# Sheet3.net
KiCad netlist of a schematic drawn in Altium Designer
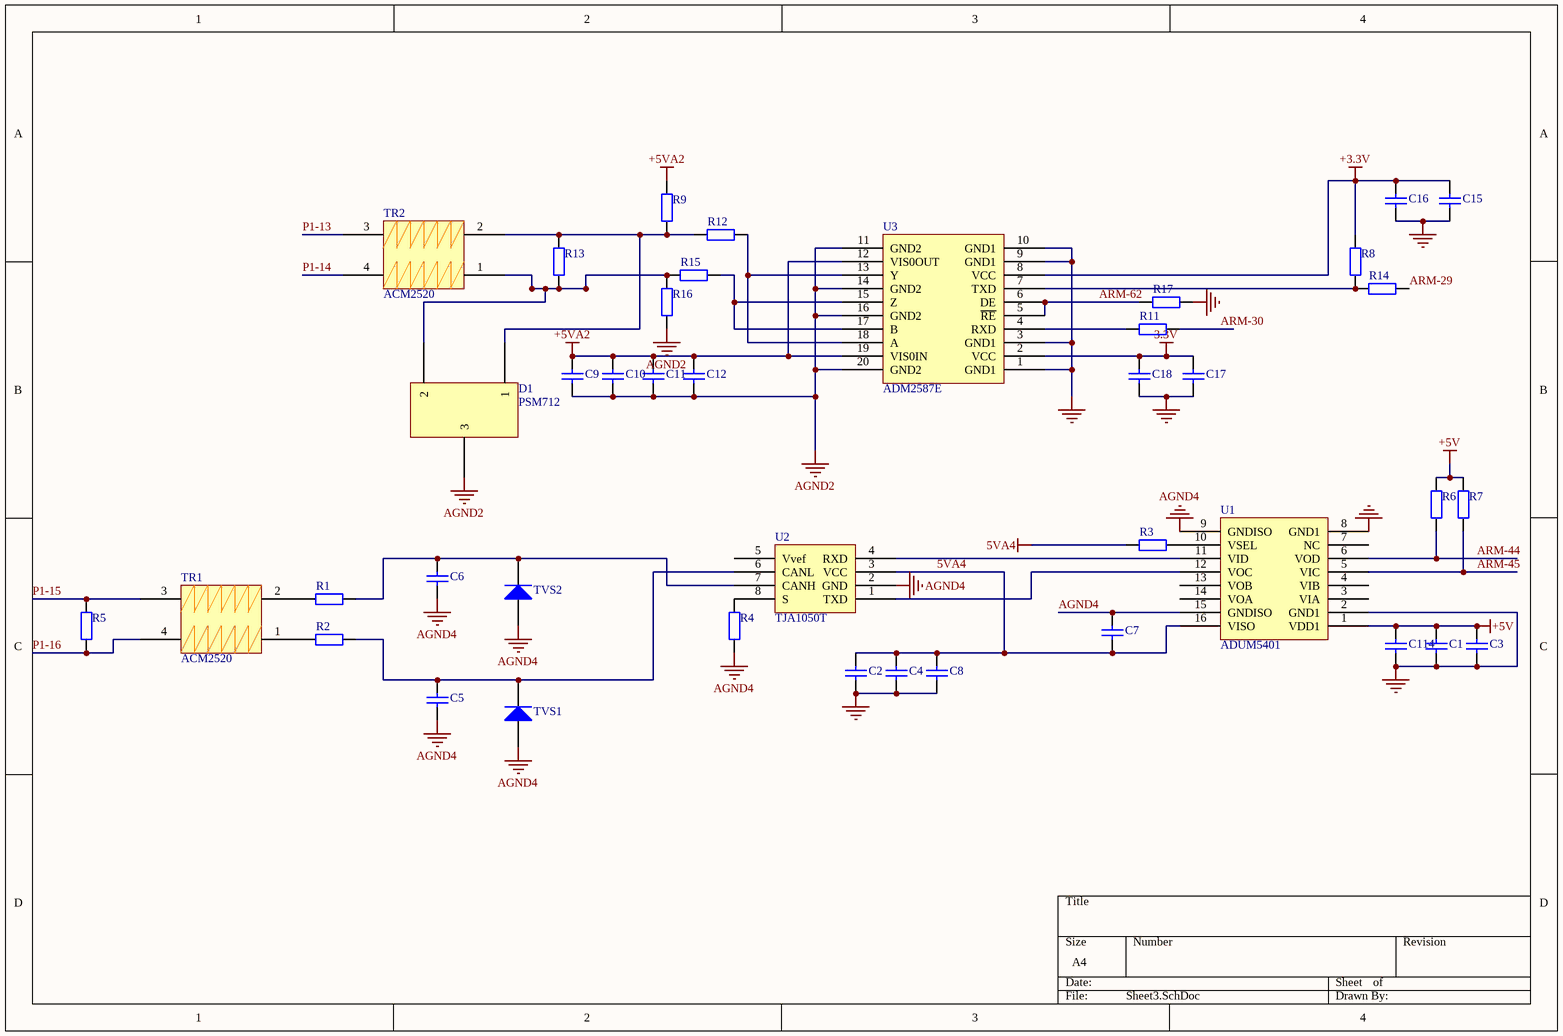
[diagram p0: Sheet3.SchDoc]

(export (version "E")
  (design (tool "Eeschema 10.0.6"))
  (components
    (comp (ref "C1")
      (value "Cap")
      (footprint "RAD-0.3")
      (description "Capacitor")
      (fields (field (name "PUBLISHER") "Altium Limited"))
      (libsource (lib "Miscellaneous Devices") (part "Cap"))
    )
    (comp (ref "C2")
      (value "Cap")
      (footprint "RAD-0.3")
      (description "Capacitor")
      (fields (field (name "PUBLISHER") "Altium Limited"))
      (libsource (lib "Miscellaneous Devices") (part "Cap"))
    )
    (comp (ref "C3")
      (value "Cap")
      (footprint "RAD-0.3")
      (description "Capacitor")
      (fields (field (name "PUBLISHER") "Altium Limited"))
      (libsource (lib "Miscellaneous Devices") (part "Cap"))
    )
    (comp (ref "C4")
      (value "Cap")
      (footprint "RAD-0.3")
      (description "Capacitor")
      (fields (field (name "PUBLISHER") "Altium Limited"))
      (libsource (lib "Miscellaneous Devices") (part "Cap"))
    )
    (comp (ref "C5")
      (value "Cap")
      (footprint "RAD-0.3")
      (description "Capacitor")
      (fields (field (name "PUBLISHER") "Altium Limited"))
      (libsource (lib "Miscellaneous Devices") (part "Cap"))
    )
    (comp (ref "C6")
      (value "Cap")
      (footprint "RAD-0.3")
      (description "Capacitor")
      (fields (field (name "PUBLISHER") "Altium Limited"))
      (libsource (lib "Miscellaneous Devices") (part "Cap"))
    )
    (comp (ref "C7")
      (value "Cap")
      (footprint "RAD-0.3")
      (description "Capacitor")
      (fields (field (name "PUBLISHER") "Altium Limited"))
      (libsource (lib "Miscellaneous Devices") (part "Cap"))
    )
    (comp (ref "C8")
      (value "Cap")
      (footprint "RAD-0.3")
      (description "Capacitor")
      (fields (field (name "PUBLISHER") "Altium Limited"))
      (libsource (lib "Miscellaneous Devices") (part "Cap"))
    )
    (comp (ref "C9")
      (value "Cap")
      (footprint "RAD-0.3")
      (description "Capacitor")
      (fields (field (name "PUBLISHER") "Altium Limited"))
      (libsource (lib "Miscellaneous Devices") (part "Cap"))
    )
    (comp (ref "C10")
      (value "Cap")
      (footprint "RAD-0.3")
      (description "Capacitor")
      (fields (field (name "PUBLISHER") "Altium Limited"))
      (libsource (lib "Miscellaneous Devices") (part "Cap"))
    )
    (comp (ref "C11")
      (value "Cap")
      (footprint "RAD-0.3")
      (description "Capacitor")
      (fields (field (name "PUBLISHER") "Altium Limited"))
      (libsource (lib "Miscellaneous Devices") (part "Cap"))
    )
    (comp (ref "C12")
      (value "Cap")
      (footprint "RAD-0.3")
      (description "Capacitor")
      (fields (field (name "PUBLISHER") "Altium Limited"))
      (libsource (lib "Miscellaneous Devices") (part "Cap"))
    )
    (comp (ref "C15")
      (value "Cap")
      (footprint "RAD-0.3")
      (description "Capacitor")
      (fields (field (name "PUBLISHER") "Altium Limited"))
      (libsource (lib "Miscellaneous Devices") (part "Cap"))
    )
    (comp (ref "C16")
      (value "Cap")
      (footprint "RAD-0.3")
      (description "Capacitor")
      (fields (field (name "PUBLISHER") "Altium Limited"))
      (libsource (lib "Miscellaneous Devices") (part "Cap"))
    )
    (comp (ref "C17")
      (value "Cap")
      (footprint "RAD-0.3")
      (description "Capacitor")
      (fields (field (name "PUBLISHER") "Altium Limited"))
      (libsource (lib "Miscellaneous Devices") (part "Cap"))
    )
    (comp (ref "C18")
      (value "Cap")
      (footprint "RAD-0.3")
      (description "Capacitor")
      (fields (field (name "PUBLISHER") "Altium Limited"))
      (libsource (lib "Miscellaneous Devices") (part "Cap"))
    )
    (comp (ref "C114")
      (value "Cap")
      (footprint "RAD-0.3")
      (description "Capacitor")
      (fields (field (name "PUBLISHER") "Altium Limited"))
      (libsource (lib "Miscellaneous Devices") (part "Cap"))
    )
    (comp (ref "D1") (value "PSM712") (libsource (lib "标准电容阵列") (part "Component_1")))
    (comp (ref "R1")
      (value "Res2")
      (footprint "AXIAL-0.4")
      (description "Resistor")
      (fields (field (name "PUBLISHER") "Altium Limited"))
      (libsource (lib "") (part "Res2_2"))
    )
    (comp (ref "R2")
      (value "Res2")
      (footprint "AXIAL-0.4")
      (description "Resistor")
      (fields (field (name "PUBLISHER") "Altium Limited"))
      (libsource (lib "") (part "Res2_2"))
    )
    (comp (ref "R3")
      (value "Res2")
      (footprint "AXIAL-0.4")
      (description "Resistor")
      (fields (field (name "PUBLISHER") "Altium Limited"))
      (libsource (lib "") (part "Res2_3"))
    )
    (comp (ref "R4")
      (value "Res2")
      (footprint "AXIAL-0.4")
      (description "Resistor")
      (fields (field (name "PUBLISHER") "Altium Limited"))
      (libsource (lib "") (part "Res2_1"))
    )
    (comp (ref "R5")
      (value "Res2")
      (footprint "AXIAL-0.4")
      (description "Resistor")
      (fields (field (name "PUBLISHER") "Altium Limited"))
      (libsource (lib "Miscellaneous Devices") (part "Res2"))
    )
    (comp (ref "R6")
      (value "Res2")
      (footprint "AXIAL-0.4")
      (description "Resistor")
      (fields (field (name "PUBLISHER") "Altium Limited"))
      (libsource (lib "Miscellaneous Devices") (part "Res2"))
    )
    (comp (ref "R7")
      (value "Res2")
      (footprint "AXIAL-0.4")
      (description "Resistor")
      (fields (field (name "PUBLISHER") "Altium Limited"))
      (libsource (lib "Miscellaneous Devices") (part "Res2"))
    )
    (comp (ref "R8")
      (value "Res2")
      (footprint "AXIAL-0.4")
      (description "Resistor")
      (fields (field (name "PUBLISHER") "Altium Limited"))
      (libsource (lib "") (part "Res2_1"))
    )
    (comp (ref "R9")
      (value "Res2")
      (footprint "AXIAL-0.4")
      (description "Resistor")
      (fields (field (name "PUBLISHER") "Altium Limited"))
      (libsource (lib "Miscellaneous Devices") (part "Res2"))
    )
    (comp (ref "R11")
      (value "Res2")
      (footprint "AXIAL-0.4")
      (description "Resistor")
      (fields (field (name "PUBLISHER") "Altium Limited"))
      (libsource (lib "") (part "Res2_2"))
    )
    (comp (ref "R12")
      (value "Res2")
      (footprint "AXIAL-0.4")
      (description "Resistor")
      (fields (field (name "PUBLISHER") "Altium Limited"))
      (libsource (lib "") (part "Res2_2"))
    )
    (comp (ref "R13")
      (value "Res2")
      (footprint "AXIAL-0.4")
      (description "Resistor")
      (fields (field (name "PUBLISHER") "Altium Limited"))
      (libsource (lib "Miscellaneous Devices") (part "Res2"))
    )
    (comp (ref "R14")
      (value "Res2")
      (footprint "AXIAL-0.4")
      (description "Resistor")
      (fields (field (name "PUBLISHER") "Altium Limited"))
      (libsource (lib "") (part "Res2_3"))
    )
    (comp (ref "R15")
      (value "Res2")
      (footprint "AXIAL-0.4")
      (description "Resistor")
      (fields (field (name "PUBLISHER") "Altium Limited"))
      (libsource (lib "") (part "Res2_2"))
    )
    (comp (ref "R16")
      (value "Res2")
      (footprint "AXIAL-0.4")
      (description "Resistor")
      (fields (field (name "PUBLISHER") "Altium Limited"))
      (libsource (lib "Miscellaneous Devices") (part "Res2"))
    )
    (comp (ref "R17")
      (value "Res2")
      (footprint "AXIAL-0.4")
      (description "Resistor")
      (fields (field (name "PUBLISHER") "Altium Limited"))
      (libsource (lib "") (part "Res2_2"))
    )
    (comp (ref "TR1") (value "ACM2520") (libsource (lib "ACM共模电感") (part "Component_1")))
    (comp (ref "TR2") (value "ACM2520") (libsource (lib "ACM共模电感") (part "Component_1")))
    (comp (ref "TVS1")
      (value "Diode 1N4007")
      (footprint "DO-41")
      (description "1 Amp General Purpose Rectifier")
      (fields (field (name "PUBLISHER") "Altium Limited"))
      (libsource (lib "Miscellaneous Devices") (part "Diode 1N4007"))
    )
    (comp (ref "TVS2")
      (value "Diode 1N4007")
      (footprint "DO-41")
      (description "1 Amp General Purpose Rectifier")
      (fields (field (name "PUBLISHER") "Altium Limited"))
      (libsource (lib "Miscellaneous Devices") (part "Diode 1N4007"))
    )
    (comp (ref "U1") (value "ADUM5401") (libsource (lib "ADUM5401") (part "Component_1")))
    (comp (ref "U2") (value "TJA1050T") (libsource (lib "TJA1050T") (part "Component_1")))
    (comp (ref "U3") (value "ADM2587E") (libsource (lib "ADM2587E") (part "Component_1")))
  )
  (nets
    (net (code "1") (name "+3.3V") (class "Default")
      (node (ref "C15") (pin "2") (pinfunction "2_2") (pintype "passive"))
      (node (ref "C16") (pin "2") (pinfunction "2_2") (pintype "passive"))
      (node (ref "R8") (pin "1") (pinfunction "1_1") (pintype "passive"))
      (node (ref "U3") (pin "8") (pinfunction "VCC_8") (pintype "passive"))
    )
    (net (code "2") (name "+5V") (class "Default")
      (node (ref "C1") (pin "2") (pinfunction "2_2") (pintype "passive"))
      (node (ref "C114") (pin "2") (pinfunction "2_2") (pintype "passive"))
      (node (ref "C3") (pin "2") (pinfunction "2_2") (pintype "passive"))
      (node (ref "R6") (pin "2") (pinfunction "2_2") (pintype "passive"))
      (node (ref "R7") (pin "2") (pinfunction "2_2") (pintype "passive"))
      (node (ref "U1") (pin "1") (pinfunction "VDD1_1") (pintype "passive"))
    )
    (net (code "3") (name "+5VA2") (class "Default")
      (node (ref "C10") (pin "2") (pinfunction "2_2") (pintype "passive"))
      (node (ref "C11") (pin "2") (pinfunction "2_2") (pintype "passive"))
      (node (ref "C12") (pin "2") (pinfunction "2_2") (pintype "passive"))
      (node (ref "C9") (pin "2") (pinfunction "2_2") (pintype "passive"))
      (node (ref "R9") (pin "2") (pinfunction "2_2") (pintype "passive"))
      (node (ref "U3") (pin "12") (pinfunction "VIS0OUT_12") (pintype "passive"))
      (node (ref "U3") (pin "19") (pinfunction "VIS0IN_19") (pintype "passive"))
    )
    (net (code "4") (name "/ARM-29") (class "Default")
      (node (ref "R14") (pin "2") (pinfunction "2_2") (pintype "passive"))
    )
    (net (code "5") (name "/ARM-30") (class "Default")
      (node (ref "R11") (pin "1") (pinfunction "1_1") (pintype "passive"))
    )
    (net (code "6") (name "/ARM-44") (class "Default")
      (node (ref "R6") (pin "1") (pinfunction "1_1") (pintype "passive"))
      (node (ref "U1") (pin "6") (pinfunction "VOD_6") (pintype "passive"))
    )
    (net (code "7") (name "/ARM-45") (class "Default")
      (node (ref "R7") (pin "1") (pinfunction "1_1") (pintype "passive"))
      (node (ref "U1") (pin "5") (pinfunction "VIC_5") (pintype "passive"))
    )
    (net (code "8") (name "/ARM-62") (class "Default")
      (node (ref "R17") (pin "2") (pinfunction "2_2") (pintype "passive"))
      (node (ref "U3") (pin "5") (pinfunction "~{RE}_5") (pintype "passive"))
      (node (ref "U3") (pin "6") (pinfunction "DE_6") (pintype "passive"))
    )
    (net (code "9") (name "/P1-13") (class "Default")
      (node (ref "TR2") (pin "3") (pinfunction "0_3") (pintype "passive"))
    )
    (net (code "10") (name "/P1-14") (class "Default")
      (node (ref "TR2") (pin "4") (pinfunction "4_4") (pintype "passive"))
    )
    (net (code "11") (name "/P1-15") (class "Default")
      (node (ref "R5") (pin "2") (pinfunction "2_2") (pintype "passive"))
      (node (ref "TR1") (pin "3") (pinfunction "0_3") (pintype "passive"))
    )
    (net (code "12") (name "/P1-16") (class "Default")
      (node (ref "R5") (pin "1") (pinfunction "1_1") (pintype "passive"))
      (node (ref "TR1") (pin "4") (pinfunction "4_4") (pintype "passive"))
    )
    (net (code "13") (name "3.3V") (class "Default")
      (node (ref "C17") (pin "2") (pinfunction "2_2") (pintype "passive"))
      (node (ref "C18") (pin "2") (pinfunction "2_2") (pintype "passive"))
      (node (ref "U3") (pin "2") (pinfunction "VCC_2") (pintype "passive"))
    )
    (net (code "14") (name "5VA4") (class "Default")
      (node (ref "C2") (pin "2") (pinfunction "2_2") (pintype "passive"))
      (node (ref "C4") (pin "2") (pinfunction "2_2") (pintype "passive"))
      (node (ref "C7") (pin "1") (pinfunction "1_1") (pintype "passive"))
      (node (ref "C8") (pin "2") (pinfunction "2_2") (pintype "passive"))
      (node (ref "R3") (pin "1") (pinfunction "1_1") (pintype "passive"))
      (node (ref "U1") (pin "16") (pinfunction "VISO_16") (pintype "passive"))
      (node (ref "U2") (pin "3") (pinfunction "VCC_3") (pintype "passive"))
    )
    (net (code "15") (name "AGND2") (class "Default")
      (node (ref "C10") (pin "1") (pinfunction "1_1") (pintype "passive"))
      (node (ref "C11") (pin "1") (pinfunction "1_1") (pintype "passive"))
      (node (ref "C12") (pin "1") (pinfunction "1_1") (pintype "passive"))
      (node (ref "C9") (pin "1") (pinfunction "1_1") (pintype "passive"))
      (node (ref "D1") (pin "3") (pinfunction "3_3") (pintype "passive"))
      (node (ref "R16") (pin "1") (pinfunction "1_1") (pintype "passive"))
      (node (ref "U3") (pin "11") (pinfunction "GND2_11") (pintype "passive"))
      (node (ref "U3") (pin "14") (pinfunction "GND2_14") (pintype "passive"))
      (node (ref "U3") (pin "16") (pinfunction "GND2_16") (pintype "passive"))
      (node (ref "U3") (pin "20") (pinfunction "GND2_20") (pintype "passive"))
    )
    (net (code "16") (name "AGND4") (class "Default")
      (node (ref "C5") (pin "1") (pinfunction "1_1") (pintype "passive"))
      (node (ref "C6") (pin "1") (pinfunction "1_1") (pintype "passive"))
      (node (ref "C7") (pin "2") (pinfunction "2_2") (pintype "passive"))
      (node (ref "R4") (pin "2") (pinfunction "2_2") (pintype "passive"))
      (node (ref "TVS1") (pin "1") (pinfunction "A_1") (pintype "passive"))
      (node (ref "TVS2") (pin "1") (pinfunction "A_1") (pintype "passive"))
      (node (ref "U1") (pin "15") (pinfunction "GNDISO_15") (pintype "passive"))
      (node (ref "U1") (pin "9") (pinfunction "GNDISO_9") (pintype "passive"))
      (node (ref "U2") (pin "2") (pinfunction "GND_2") (pintype "passive"))
    )
    (net (code "17") (name "GND") (class "Default")
      (node (ref "C1") (pin "1") (pinfunction "1_1") (pintype "passive"))
      (node (ref "C114") (pin "1") (pinfunction "1_1") (pintype "passive"))
      (node (ref "C15") (pin "1") (pinfunction "1_1") (pintype "passive"))
      (node (ref "C16") (pin "1") (pinfunction "1_1") (pintype "passive"))
      (node (ref "C17") (pin "1") (pinfunction "1_1") (pintype "passive"))
      (node (ref "C18") (pin "1") (pinfunction "1_1") (pintype "passive"))
      (node (ref "C2") (pin "1") (pinfunction "1_1") (pintype "passive"))
      (node (ref "C3") (pin "1") (pinfunction "1_1") (pintype "passive"))
      (node (ref "C4") (pin "1") (pinfunction "1_1") (pintype "passive"))
      (node (ref "C8") (pin "1") (pinfunction "1_1") (pintype "passive"))
      (node (ref "R17") (pin "1") (pinfunction "1_1") (pintype "passive"))
      (node (ref "U1") (pin "2") (pinfunction "GND1_2") (pintype "passive"))
      (node (ref "U1") (pin "8") (pinfunction "GND1_8") (pintype "passive"))
      (node (ref "U3") (pin "1") (pinfunction "GND1_1") (pintype "passive"))
      (node (ref "U3") (pin "10") (pinfunction "GND1_10") (pintype "passive"))
      (node (ref "U3") (pin "3") (pinfunction "GND1_3") (pintype "passive"))
      (node (ref "U3") (pin "9") (pinfunction "GND1_9") (pintype "passive"))
    )
    (net (code "18") (name "Net-(D1-2)") (class "Default")
      (node (ref "D1") (pin "0") (pinfunction "2_0") (pintype "passive"))
      (node (ref "R13") (pin "1") (pinfunction "1_1") (pintype "passive"))
      (node (ref "R15") (pin "2") (pinfunction "2_2") (pintype "passive"))
      (node (ref "R16") (pin "2") (pinfunction "2_2") (pintype "passive"))
      (node (ref "TR2") (pin "1") (pinfunction "3_1") (pintype "passive"))
    )
    (net (code "19") (name "Net-(D1-Pad1)") (class "Default")
      (node (ref "D1") (pin "1") (pinfunction "1_1") (pintype "passive"))
      (node (ref "R12") (pin "2") (pinfunction "2_2") (pintype "passive"))
      (node (ref "R13") (pin "2") (pinfunction "2_2") (pintype "passive"))
      (node (ref "R9") (pin "1") (pinfunction "1_1") (pintype "passive"))
      (node (ref "TR2") (pin "2") (pinfunction "2_2") (pintype "passive"))
    )
    (net (code "20") (name "Net-(R1-Pad2)") (class "Default")
      (node (ref "R1") (pin "2") (pinfunction "2_2") (pintype "passive"))
      (node (ref "TR1") (pin "2") (pinfunction "2_2") (pintype "passive"))
    )
    (net (code "21") (name "Net-(TR1-3)") (class "Default")
      (node (ref "R2") (pin "2") (pinfunction "2_2") (pintype "passive"))
      (node (ref "TR1") (pin "1") (pinfunction "3_1") (pintype "passive"))
    )
    (net (code "22") (name "Net-(TVS1-K)") (class "Default")
      (node (ref "C5") (pin "2") (pinfunction "2_2") (pintype "passive"))
      (node (ref "R2") (pin "1") (pinfunction "1_1") (pintype "passive"))
      (node (ref "TVS1") (pin "2") (pinfunction "K_2") (pintype "passive"))
      (node (ref "U2") (pin "6") (pinfunction "CANL_6") (pintype "passive"))
    )
    (net (code "23") (name "Net-(TVS2-K)") (class "Default")
      (node (ref "C6") (pin "2") (pinfunction "2_2") (pintype "passive"))
      (node (ref "R1") (pin "1") (pinfunction "1_1") (pintype "passive"))
      (node (ref "TVS2") (pin "2") (pinfunction "K_2") (pintype "passive"))
      (node (ref "U2") (pin "7") (pinfunction "CANH_7") (pintype "passive"))
    )
    (net (code "24") (name "Net-(U1-VID)") (class "Default")
      (node (ref "U1") (pin "11") (pinfunction "VID_11") (pintype "passive"))
      (node (ref "U2") (pin "4") (pinfunction "RXD_4") (pintype "passive"))
    )
    (net (code "25") (name "Net-(U1-VOC)") (class "Default")
      (node (ref "U1") (pin "12") (pinfunction "VOC_12") (pintype "passive"))
      (node (ref "U2") (pin "1") (pinfunction "TXD_1") (pintype "passive"))
    )
    (net (code "26") (name "Net-(U1-VSEL)") (class "Default")
      (node (ref "R3") (pin "2") (pinfunction "2_2") (pintype "passive"))
      (node (ref "U1") (pin "10") (pinfunction "VSEL_10") (pintype "passive"))
    )
    (net (code "27") (name "Net-(U2-S)") (class "Default")
      (node (ref "R4") (pin "1") (pinfunction "1_1") (pintype "passive"))
      (node (ref "U2") (pin "8") (pinfunction "S_8") (pintype "passive"))
    )
    (net (code "28") (name "Net-(U3-A)") (class "Default")
      (node (ref "R12") (pin "1") (pinfunction "1_1") (pintype "passive"))
      (node (ref "U3") (pin "13") (pinfunction "Y_13") (pintype "passive"))
      (node (ref "U3") (pin "18") (pinfunction "A_18") (pintype "passive"))
    )
    (net (code "29") (name "Net-(U3-B)") (class "Default")
      (node (ref "R15") (pin "1") (pinfunction "1_1") (pintype "passive"))
      (node (ref "U3") (pin "15") (pinfunction "Z_15") (pintype "passive"))
      (node (ref "U3") (pin "17") (pinfunction "B_17") (pintype "passive"))
    )
    (net (code "30") (name "Net-(U3-RXD)") (class "Default")
      (node (ref "R11") (pin "2") (pinfunction "2_2") (pintype "passive"))
      (node (ref "U3") (pin "4") (pinfunction "RXD_4") (pintype "passive"))
    )
    (net (code "31") (name "Net-(U3-TXD)") (class "Default")
      (node (ref "R14") (pin "1") (pinfunction "1_1") (pintype "passive"))
      (node (ref "R8") (pin "2") (pinfunction "2_2") (pintype "passive"))
      (node (ref "U3") (pin "7") (pinfunction "TXD_7") (pintype "passive"))
    )
    (net (code "32") (name "unconnected-(U1-NC-Pad7)") (class "Default")
      (node (ref "U1") (pin "7") (pinfunction "NC_7") (pintype "passive"))
    )
    (net (code "33") (name "unconnected-(U1-VIA-Pad3)") (class "Default")
      (node (ref "U1") (pin "3") (pinfunction "VIA_3") (pintype "passive"))
    )
    (net (code "34") (name "unconnected-(U1-VIB-Pad4)") (class "Default")
      (node (ref "U1") (pin "4") (pinfunction "VIB_4") (pintype "passive"))
    )
    (net (code "35") (name "unconnected-(U1-VOA-Pad14)") (class "Default")
      (node (ref "U1") (pin "14") (pinfunction "VOA_14") (pintype "passive"))
    )
    (net (code "36") (name "unconnected-(U1-VOB-Pad13)") (class "Default")
      (node (ref "U1") (pin "13") (pinfunction "VOB_13") (pintype "passive"))
    )
    (net (code "37") (name "unconnected-(U2-Vvef-Pad5)") (class "Default")
      (node (ref "U2") (pin "5") (pinfunction "Vvef_5") (pintype "passive"))
    )
  )
)
